# oysm_Keyboard_Power_supply.net
KiCad netlist of a schematic drawn in Altium Designer
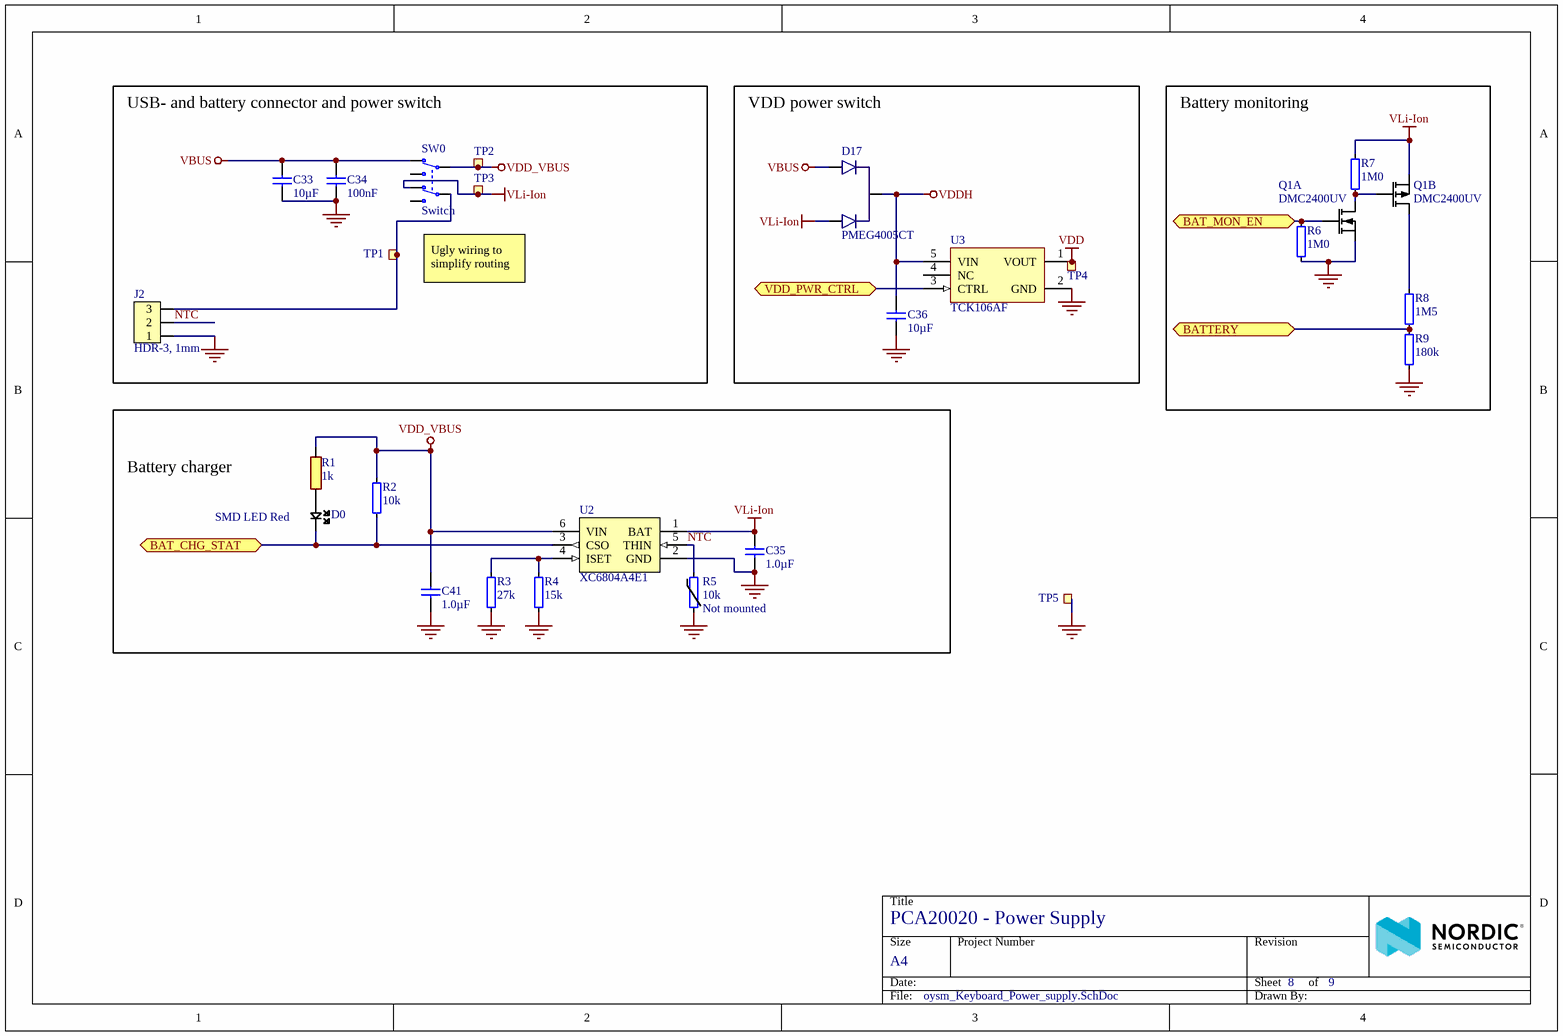
[diagram p0: oysm_Keyboard_Power_supply.SchDoc]

(export (version "E")
  (design (tool "Eeschema 10.0.6"))
  (components
    (comp (ref "C33")
      (value "10µF")
      (footprint "CAPC1608X06L")
      (description "Capacitor, X5R, ±20%")
      (fields (field (name "PART NUMBER") "C0603-10µ") (field (name "PUBLISHER") "Nordic Semiconductor"))
      (libsource (lib "Nordic Passive DB") (part "CAP"))
    )
    (comp (ref "C34")
      (value "100nF")
      (footprint "CAPC1005X04L")
      (description "Capacitor, X7R, ±10%")
      (fields (field (name "PART NUMBER") "C0402-100n") (field (name "PUBLISHER") "Nordic Semiconductor"))
      (libsource (lib "Nordic Passive DB") (part "CAP"))
    )
    (comp (ref "C35")
      (value "1.0µF")
      (footprint "CAPC1608X06L")
      (description "Capacitor, X7R, ±10%")
      (fields (field (name "PART NUMBER") "C0603-1µ0") (field (name "PUBLISHER") "Nordic Semiconductor"))
      (libsource (lib "Nordic Passive DB") (part "CAP"))
    )
    (comp (ref "C36")
      (value "10µF")
      (footprint "CAPC1608X06L")
      (description "Capacitor, X5R, ±20%")
      (fields (field (name "PART NUMBER") "C0603-10µ") (field (name "PUBLISHER") "Nordic Semiconductor"))
      (libsource (lib "Nordic Passive DB") (part "CAP"))
    )
    (comp (ref "C41")
      (value "1.0µF")
      (footprint "CAPC1608X06L")
      (description "Capacitor, X7R, ±10%")
      (fields (field (name "PART NUMBER") "C0603-1µ0") (field (name "PUBLISHER") "Nordic Semiconductor"))
      (libsource (lib "Nordic Passive DB") (part "CAP"))
    )
    (comp (ref "D0")
      (value "SMD LED Red")
      (footprint "I_LEDC0603(1608)_N")
      (description "SMD")
      (libsource (lib "OVLib_64") (part "LED"))
    )
    (comp (ref "D17")
      (value "PMEG4005CT")
      (footprint "SOT95P230X110-3N")
      (libsource (lib "PMEG4005CT") (part "PMEG4005CT"))
    )
    (comp (ref "J2")
      (value "HDR-3, 1mm")
      (footprint "SM03B-SRSS-TB")
      (description "1.0mm pitch connector side entry SMD")
      (fields
        (field (name "PART NUMBER") "SM03B-SRSS-TB")
        (field (name "MANUFACTURER") "JST")
        (field (name "PUBLISHER") "Nordic Semiconductor")
      )
      (libsource (lib "Nordic Passive DB") (part "CONN-3"))
    )
    (comp (ref "Q1")
      (value "DMC2400UV")
      (footprint "SOTFL50P162X60-6N")
      (description "Dual N & P Ch MOFET, 1.03A/0.7A, 480mOhm, 450mW")
      (fields
        (field (name "MANUFACTURER") "Diodes Incorporated")
        (field (name "PUBLISHER") "Nordic Semiconductor")
      )
      (libsource (lib "Nordic Discrete DB") (part "T{colon}FET-N/P-DUAL"))
    )
    (comp (ref "R1")
      (value "1k")
      (footprint "RESC0603(1608)_N")
      (description "0.1W 1% Thick film resistor")
      (libsource (lib "OVLib_64") (part "Resistor2"))
    )
    (comp (ref "R2")
      (value "10k")
      (footprint "RESC1005X04L")
      (description "Resistor, ±1%, 0.063W")
      (fields (field (name "PART NUMBER") "R0402-10k") (field (name "PUBLISHER") "Nordic Semiconductor"))
      (libsource (lib "Nordic Passive DB") (part "RES_1"))
    )
    (comp (ref "R3")
      (value "27k")
      (footprint "RESC1005X04L")
      (description "Resistor, ±1%, 0.063W")
      (fields (field (name "PART NUMBER") "R0402-27k") (field (name "PUBLISHER") "Nordic Semiconductor"))
      (libsource (lib "Nordic Passive DB") (part "RES_1"))
    )
    (comp (ref "R4")
      (value "15k")
      (footprint "RESC1005X04L")
      (description "Resistor, ±1%, 0.063W")
      (fields (field (name "PART NUMBER") "R0402-15k") (field (name "PUBLISHER") "Nordic Semiconductor"))
      (libsource (lib "Nordic Passive DB") (part "RES_1"))
    )
    (comp (ref "R5")
      (value "10k")
      (footprint "RESC1005X04L")
      (description "THERMISTOR 10K OHM NTC 0402 SMD")
      (fields
        (field (name "PART NUMBER") "NCP15XH103F03RC")
        (field (name "MANUFACTURER") "Murata")
        (field (name "ASSEMBLY") "Not mounted")
        (field (name "PUBLISHER") "Nordic Semiconductor")
      )
      (libsource (lib "Nordic Passive DB") (part "RES_NTC"))
    )
    (comp (ref "R6")
      (value "1M0")
      (footprint "RESC1005X04L")
      (description "Resistor, ±1%, 0.063W")
      (fields (field (name "PART NUMBER") "R0402-1M0") (field (name "PUBLISHER") "Nordic Semiconductor"))
      (libsource (lib "Nordic Passive DB") (part "RES_1"))
    )
    (comp (ref "R7")
      (value "1M0")
      (footprint "RESC1005X04L")
      (description "Resistor, ±1%, 0.063W")
      (fields (field (name "PART NUMBER") "R0402-1M0") (field (name "PUBLISHER") "Nordic Semiconductor"))
      (libsource (lib "Nordic Passive DB") (part "RES_1"))
    )
    (comp (ref "R8")
      (value "1M5")
      (footprint "RESC1005X04L")
      (description "Resistor, ±1%, 0.063W")
      (fields (field (name "PART NUMBER") "R0402-1M5") (field (name "PUBLISHER") "Nordic Semiconductor"))
      (libsource (lib "Nordic Passive DB") (part "RES_1"))
    )
    (comp (ref "R9")
      (value "180k")
      (footprint "RESC1005X04L")
      (description "Resistor, ±1%, 0.063W")
      (fields (field (name "PART NUMBER") "R0402-180k") (field (name "PUBLISHER") "Nordic Semiconductor"))
      (libsource (lib "Nordic Passive DB") (part "RES_1"))
    )
    (comp (ref "SW0")
      (value "Switch")
      (footprint "Switch-Slide-RA-J-Lead-DPDT-8.5x3.5mm")
      (description "SMD slide Switch (ON-ON)")
      (fields
        (field (name "PART NUMBER") "Switch-Slide-RA-J-Lead-DPDT-8.5x3.5mm_C&K")
        (field (name "MANUFACTURER") "C&K Components")
        (field (name "PUBLISHER") "Nordic Semiconductor")
      )
      (libsource (lib "Nordic Discrete DB") (part "SW-DPDT"))
    )
    (comp (ref "TP1")
      (value "Ø1.5mm,SMD")
      (footprint "TP_SMD_Ø1.5mm")
      (description "1.0mm circular SMD testpad")
      (fields
        (field (name "PART NUMBER") "TP_SMD_Ø1.5MM")
        (field (name "MANUFACTURER") "Nordic Semiconductor")
        (field (name "PUBLISHER") "Nordic Semiconductor")
      )
      (libsource (lib "") (part "TESTPAD_2"))
    )
    (comp (ref "TP2")
      (value "Ø1.5mm,SMD")
      (footprint "TP_SMD_Ø1.5mm")
      (description "1.0mm circular SMD testpad")
      (fields
        (field (name "PART NUMBER") "TP_SMD_Ø1.5MM")
        (field (name "MANUFACTURER") "Nordic Semiconductor")
        (field (name "PUBLISHER") "Nordic Semiconductor")
      )
      (libsource (lib "Nordic Passive DB") (part "TESTPAD"))
    )
    (comp (ref "TP3")
      (value "Ø1.5mm,SMD")
      (footprint "TP_SMD_Ø1.5mm")
      (description "1.0mm circular SMD testpad")
      (fields
        (field (name "PART NUMBER") "TP_SMD_Ø1.5MM")
        (field (name "MANUFACTURER") "Nordic Semiconductor")
        (field (name "PUBLISHER") "Nordic Semiconductor")
      )
      (libsource (lib "Nordic Passive DB") (part "TESTPAD"))
    )
    (comp (ref "TP4")
      (value "Ø1.5mm,SMD")
      (footprint "TP_SMD_Ø1.5mm")
      (description "1.0mm circular SMD testpad")
      (fields
        (field (name "PART NUMBER") "TP_SMD_Ø1.5MM")
        (field (name "MANUFACTURER") "Nordic Semiconductor")
        (field (name "PUBLISHER") "Nordic Semiconductor")
      )
      (libsource (lib "") (part "TESTPAD_1"))
    )
    (comp (ref "TP5")
      (value "Ø1.5mm,SMD")
      (footprint "TP_SMD_Ø1.5mm")
      (description "1.0mm circular SMD testpad")
      (fields
        (field (name "PART NUMBER") "TP_SMD_Ø1.5MM")
        (field (name "MANUFACTURER") "Nordic Semiconductor")
        (field (name "PUBLISHER") "Nordic Semiconductor")
      )
      (libsource (lib "") (part "TESTPAD_2"))
    )
    (comp (ref "U2")
      (value "XC6804A4E1")
      (footprint "USP-6EL")
      (description "One Cell Li-ion/Li-polymer Linear Charger IC with Battery Temperature Detection")
      (fields
        (field (name "PART NUMBER") "XC6804A4E14R-G")
        (field (name "MANUFACTURER") "Torex Semiconductor")
        (field (name "PUBLISHER") "Nordic Semiconductor")
      )
      (libsource (lib "Nordic Active DB") (part "XC6804"))
    )
    (comp (ref "U3")
      (value "TCK106AF")
      (footprint "SOT95P280X140-5N")
      (description "1.0 A Load Switch IC with Slew Rate Control Driver in Small Package")
      (fields
        (field (name "PART NUMBER") "TCK106AF,LF")
        (field (name "MANUFACTURER") "Toshiba")
        (field (name "PUBLISHER") "Nordic Semiconductor")
      )
      (libsource (lib "Nordic Active DB") (part "TCK10xAF"))
    )
  )
  (nets
    (net (code "1") (name "/BATTERY") (class "Default")
      (node (ref "R8") (pin "2") (pinfunction "2_2") (pintype "passive"))
      (node (ref "R9") (pin "1") (pinfunction "1_1") (pintype "passive"))
    )
    (net (code "2") (name "/BAT_CHG_STAT") (class "Default")
      (node (ref "D0") (pin "2") (pinfunction "2_2") (pintype "passive"))
      (node (ref "R2") (pin "2") (pinfunction "2_2") (pintype "passive"))
      (node (ref "U2") (pin "3") (pinfunction "CSO_3") (pintype "output"))
    )
    (net (code "3") (name "/BAT_MON_EN") (class "Default")
      (node (ref "Q1") (pin "2") (pinfunction "G1_2") (pintype "passive"))
      (node (ref "R6") (pin "1") (pinfunction "1_1") (pintype "passive"))
    )
    (net (code "4") (name "/NTC") (class "Default")
      (node (ref "J2") (pin "2") (pinfunction "2_2") (pintype "passive"))
      (node (ref "R5") (pin "1") (pinfunction "1_1") (pintype "passive"))
      (node (ref "U2") (pin "5") (pinfunction "THIN_5") (pintype "input"))
    )
    (net (code "5") (name "/VDD_PWR_CTRL") (class "Default")
      (node (ref "U3") (pin "3") (pinfunction "CTRL_3") (pintype "input"))
    )
    (net (code "6") (name "GND") (class "Default")
      (node (ref "C33") (pin "2") (pinfunction "2_2") (pintype "passive"))
      (node (ref "C34") (pin "2") (pinfunction "2_2") (pintype "passive"))
      (node (ref "C35") (pin "1") (pinfunction "1_1") (pintype "passive"))
      (node (ref "C36") (pin "1") (pinfunction "1_1") (pintype "passive"))
      (node (ref "C41") (pin "1") (pinfunction "1_1") (pintype "passive"))
      (node (ref "J2") (pin "1") (pinfunction "1_1") (pintype "passive"))
      (node (ref "Q1") (pin "1") (pinfunction "S1_1") (pintype "passive"))
      (node (ref "R3") (pin "2") (pinfunction "2_2") (pintype "passive"))
      (node (ref "R4") (pin "2") (pinfunction "2_2") (pintype "passive"))
      (node (ref "R5") (pin "2") (pinfunction "2_2") (pintype "passive"))
      (node (ref "R6") (pin "2") (pinfunction "2_2") (pintype "passive"))
      (node (ref "R9") (pin "2") (pinfunction "2_2") (pintype "passive"))
      (node (ref "TP5") (pin "1") (pinfunction "1_1") (pintype "passive"))
      (node (ref "U2") (pin "2") (pinfunction "GND_2") (pintype "power_in"))
      (node (ref "U2") (pin "7") (pinfunction "GND_7") (pintype "power_in"))
      (node (ref "U3") (pin "2") (pinfunction "GND_2") (pintype "power_in"))
    )
    (net (code "7") (name "Net-(D0-Pad1)") (class "Default")
      (node (ref "D0") (pin "1") (pinfunction "1_1") (pintype "passive"))
      (node (ref "R1") (pin "1") (pinfunction "1_1") (pintype "passive"))
    )
    (net (code "8") (name "Net-(Q1A-D1)") (class "Default")
      (node (ref "Q1") (pin "5") (pinfunction "G2_5") (pintype "passive"))
      (node (ref "Q1") (pin "6") (pinfunction "D1_6") (pintype "passive"))
      (node (ref "R7") (pin "2") (pinfunction "2_2") (pintype "passive"))
    )
    (net (code "9") (name "Net-(Q1B-D2)") (class "Default")
      (node (ref "Q1") (pin "3") (pinfunction "D2_3") (pintype "passive"))
      (node (ref "R8") (pin "1") (pinfunction "1_1") (pintype "passive"))
    )
    (net (code "10") (name "Net-(SW0-COM-2)") (class "Default")
      (node (ref "J2") (pin "3") (pinfunction "3_3") (pintype "passive"))
      (node (ref "SW0") (pin "5") (pinfunction "COM-2_5") (pintype "passive"))
      (node (ref "TP1") (pin "1") (pinfunction "1_1") (pintype "passive"))
    )
    (net (code "11") (name "Net-(U2-ISET)") (class "Default")
      (node (ref "R3") (pin "1") (pinfunction "1_1") (pintype "passive"))
      (node (ref "R4") (pin "1") (pinfunction "1_1") (pintype "passive"))
      (node (ref "U2") (pin "4") (pinfunction "ISET_4") (pintype "input"))
    )
    (net (code "12") (name "VBUS") (class "Default")
      (node (ref "C33") (pin "1") (pinfunction "1_1") (pintype "passive"))
      (node (ref "C34") (pin "1") (pinfunction "1_1") (pintype "passive"))
      (node (ref "D17") (pin "2") (pinfunction "A_2") (pintype "passive"))
      (node (ref "SW0") (pin "3") (pinfunction "N.C-1_3") (pintype "passive"))
    )
    (net (code "13") (name "VDD") (class "Default")
      (node (ref "TP4") (pin "1") (pinfunction "1_1") (pintype "passive"))
      (node (ref "U3") (pin "1") (pinfunction "VOUT_1") (pintype "power_in"))
    )
    (net (code "14") (name "VDDH") (class "Default")
      (node (ref "C36") (pin "2") (pinfunction "2_2") (pintype "passive"))
      (node (ref "D17") (pin "3") (pinfunction "C_3") (pintype "passive"))
      (node (ref "U3") (pin "5") (pinfunction "VIN_5") (pintype "power_in"))
    )
    (net (code "15") (name "VDD_VBUS") (class "Default")
      (node (ref "C41") (pin "2") (pinfunction "2_2") (pintype "passive"))
      (node (ref "R1") (pin "2") (pinfunction "2_2") (pintype "passive"))
      (node (ref "R2") (pin "1") (pinfunction "1_1") (pintype "passive"))
      (node (ref "SW0") (pin "2") (pinfunction "COM-1_2") (pintype "passive"))
      (node (ref "TP2") (pin "1") (pinfunction "1_1") (pintype "passive"))
      (node (ref "U2") (pin "6") (pinfunction "VIN_6") (pintype "power_in"))
    )
    (net (code "16") (name "VLi-Ion") (class "Default")
      (node (ref "C35") (pin "2") (pinfunction "2_2") (pintype "passive"))
      (node (ref "D17") (pin "1") (pinfunction "A_1") (pintype "passive"))
      (node (ref "Q1") (pin "4") (pinfunction "S2_4") (pintype "passive"))
      (node (ref "R7") (pin "1") (pinfunction "1_1") (pintype "passive"))
      (node (ref "SW0") (pin "6") (pinfunction "N.C-2_6") (pintype "passive"))
      (node (ref "TP3") (pin "1") (pinfunction "1_1") (pintype "passive"))
      (node (ref "U2") (pin "1") (pinfunction "BAT_1") (pintype "power_in"))
    )
    (net (code "17") (name "unconnected-(SW0-N.O-1-Pad1)") (class "Default")
      (node (ref "SW0") (pin "1") (pinfunction "N.O-1_1") (pintype "passive"))
    )
    (net (code "18") (name "unconnected-(SW0-N.O-2-Pad4)") (class "Default")
      (node (ref "SW0") (pin "4") (pinfunction "N.O-2_4") (pintype "passive"))
    )
    (net (code "19") (name "unconnected-(U3-NC-Pad4)") (class "Default")
      (node (ref "U3") (pin "4") (pinfunction "NC_4") (pintype "passive"))
    )
  )
)
